# SNES_to_NES.net
KiCad netlist of a schematic drawn in EAGLE
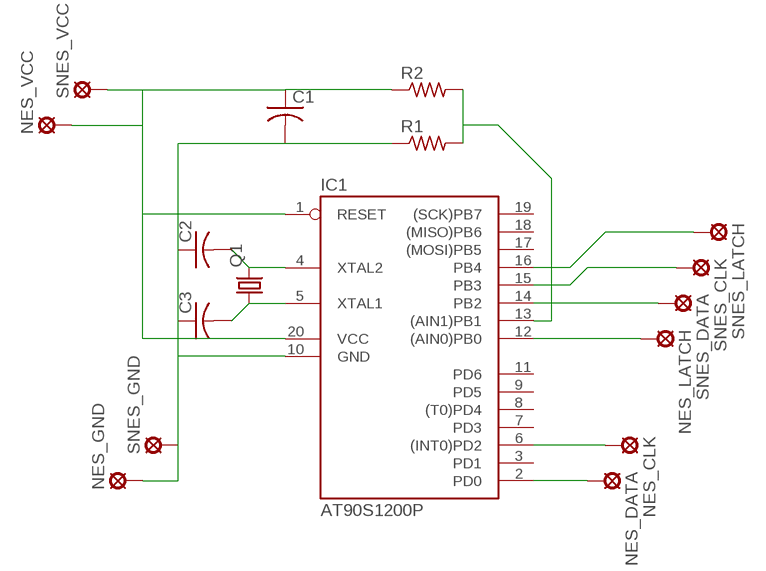
[diagram p0: schematic, sheet 1]

(export (version "E")
  (design (tool "Eeschema 10.0.6"))
  (components
    (comp (ref "C1")
      (value "C-US025_050-035X075")
      (footprint "eagle-import:C025_050-035X075")
      (libsource (lib "eagle-import") (part "C-US025_050-035X075"))
    )
    (comp (ref "C2")
      (value "C-US025-030X050")
      (footprint "eagle-import:C025-030X050")
      (libsource (lib "eagle-import") (part "C-US025-030X050"))
    )
    (comp (ref "C3")
      (value "C-US025-030X050")
      (footprint "eagle-import:C025-030X050")
      (libsource (lib "eagle-import") (part "C-US025-030X050"))
    )
    (comp (ref "IC1")
      (value "AT90S1200P")
      (footprint "eagle-import:DIL20")
      (libsource (lib "eagle-import") (part "AT90S1200P"))
    )
    (comp (ref "NES_CLK")
      (value "MCS08")
      (footprint "eagle-import:MCS08")
      (libsource (lib "eagle-import") (part "MCS08"))
    )
    (comp (ref "NES_DATA")
      (value "MCS08")
      (footprint "eagle-import:MCS08")
      (libsource (lib "eagle-import") (part "MCS08"))
    )
    (comp (ref "NES_GND")
      (value "MCS08")
      (footprint "eagle-import:MCS08")
      (libsource (lib "eagle-import") (part "MCS08"))
    )
    (comp (ref "NES_LATCH")
      (value "MCS08")
      (footprint "eagle-import:MCS08")
      (libsource (lib "eagle-import") (part "MCS08"))
    )
    (comp (ref "NES_VCC")
      (value "MCS08")
      (footprint "eagle-import:MCS08")
      (libsource (lib "eagle-import") (part "MCS08"))
    )
    (comp (ref "Q1")
      (value "CRYSTALHC49U-H")
      (footprint "eagle-import:HC49U-H")
      (libsource (lib "eagle-import") (part "CRYSTALHC49U-H"))
    )
    (comp (ref "R1")
      (value "R-US_0207/7")
      (footprint "eagle-import:0207_7")
      (libsource (lib "eagle-import") (part "R-US_0207/7"))
    )
    (comp (ref "R2")
      (value "R-US_0207/7")
      (footprint "eagle-import:0207_7")
      (libsource (lib "eagle-import") (part "R-US_0207/7"))
    )
    (comp (ref "SNES_CLK")
      (value "MCS08")
      (footprint "eagle-import:MCS08")
      (libsource (lib "eagle-import") (part "MCS08"))
    )
    (comp (ref "SNES_DATA")
      (value "MCS08")
      (footprint "eagle-import:MCS08")
      (libsource (lib "eagle-import") (part "MCS08"))
    )
    (comp (ref "SNES_GND")
      (value "MCS08")
      (footprint "eagle-import:MCS08")
      (libsource (lib "eagle-import") (part "MCS08"))
    )
    (comp (ref "SNES_LATCH")
      (value "MCS08")
      (footprint "eagle-import:MCS08")
      (libsource (lib "eagle-import") (part "MCS08"))
    )
    (comp (ref "SNES_VCC")
      (value "MCS08")
      (footprint "eagle-import:MCS08")
      (libsource (lib "eagle-import") (part "MCS08"))
    )
  )
  (nets
    (net (code "1") (name "Net-(IC1-(AIN0)PB0)") (class "Default")
      (node (ref "IC1") (pin "12") (pinfunction "(AIN0)PB0_12") (pintype "bidirectional"))
      (node (ref "NES_LATCH") (pin "MP") (pinfunction "MP_MP") (pintype "passive"))
    )
    (net (code "2") (name "Net-(IC1-(AIN1)PB1)") (class "Default")
      (node (ref "IC1") (pin "13") (pinfunction "(AIN1)PB1_13") (pintype "bidirectional"))
      (node (ref "R1") (pin "2") (pinfunction "2_2") (pintype "passive"))
      (node (ref "R2") (pin "2") (pinfunction "2_2") (pintype "passive"))
    )
    (net (code "3") (name "Net-(IC1-(INT0)PD2)") (class "Default")
      (node (ref "IC1") (pin "6") (pinfunction "(INT0)PD2_6") (pintype "bidirectional"))
      (node (ref "NES_CLK") (pin "MP") (pinfunction "MP_MP") (pintype "passive"))
    )
    (net (code "4") (name "Net-(IC1-GND)") (class "Default")
      (node (ref "C1") (pin "2") (pinfunction "2_2") (pintype "passive"))
      (node (ref "C2") (pin "1") (pinfunction "1_1") (pintype "passive"))
      (node (ref "C3") (pin "1") (pinfunction "1_1") (pintype "passive"))
      (node (ref "IC1") (pin "10") (pinfunction "GND_10") (pintype "power_in"))
      (node (ref "NES_GND") (pin "MP") (pinfunction "MP_MP") (pintype "passive"))
      (node (ref "R1") (pin "1") (pinfunction "1_1") (pintype "passive"))
      (node (ref "SNES_GND") (pin "MP") (pinfunction "MP_MP") (pintype "passive"))
    )
    (net (code "5") (name "Net-(IC1-PB2)") (class "Default")
      (node (ref "IC1") (pin "14") (pinfunction "PB2_14") (pintype "bidirectional"))
      (node (ref "SNES_DATA") (pin "MP") (pinfunction "MP_MP") (pintype "passive"))
    )
    (net (code "6") (name "Net-(IC1-PB3)") (class "Default")
      (node (ref "IC1") (pin "15") (pinfunction "PB3_15") (pintype "bidirectional"))
      (node (ref "SNES_CLK") (pin "MP") (pinfunction "MP_MP") (pintype "passive"))
    )
    (net (code "7") (name "Net-(IC1-PB4)") (class "Default")
      (node (ref "IC1") (pin "16") (pinfunction "PB4_16") (pintype "bidirectional"))
      (node (ref "SNES_LATCH") (pin "MP") (pinfunction "MP_MP") (pintype "passive"))
    )
    (net (code "8") (name "Net-(IC1-PD0)") (class "Default")
      (node (ref "IC1") (pin "2") (pinfunction "PD0_2") (pintype "bidirectional"))
      (node (ref "NES_DATA") (pin "MP") (pinfunction "MP_MP") (pintype "passive"))
    )
    (net (code "9") (name "Net-(IC1-RESET)") (class "Default")
      (node (ref "C1") (pin "1") (pinfunction "1_1") (pintype "passive"))
      (node (ref "IC1") (pin "1") (pinfunction "RESET_1") (pintype "bidirectional"))
      (node (ref "IC1") (pin "20") (pinfunction "VCC_20") (pintype "power_in"))
      (node (ref "NES_VCC") (pin "MP") (pinfunction "MP_MP") (pintype "passive"))
      (node (ref "R2") (pin "1") (pinfunction "1_1") (pintype "passive"))
      (node (ref "SNES_VCC") (pin "MP") (pinfunction "MP_MP") (pintype "passive"))
    )
    (net (code "10") (name "Net-(IC1-XTAL1)") (class "Default")
      (node (ref "C3") (pin "2") (pinfunction "2_2") (pintype "passive"))
      (node (ref "IC1") (pin "5") (pinfunction "XTAL1_5") (pintype "bidirectional"))
      (node (ref "Q1") (pin "1") (pinfunction "1_1") (pintype "passive"))
    )
    (net (code "11") (name "Net-(IC1-XTAL2)") (class "Default")
      (node (ref "C2") (pin "2") (pinfunction "2_2") (pintype "passive"))
      (node (ref "IC1") (pin "4") (pinfunction "XTAL2_4") (pintype "bidirectional"))
      (node (ref "Q1") (pin "2") (pinfunction "2_2") (pintype "passive"))
    )
    (net (code "12") (name "unconnected-(IC1-(MISO)PB6-Pad18)") (class "Default")
      (node (ref "IC1") (pin "18") (pinfunction "(MISO)PB6_18") (pintype "bidirectional"))
    )
    (net (code "13") (name "unconnected-(IC1-(MOSI)PB5-Pad17)") (class "Default")
      (node (ref "IC1") (pin "17") (pinfunction "(MOSI)PB5_17") (pintype "bidirectional"))
    )
    (net (code "14") (name "unconnected-(IC1-(SCK)PB7-Pad19)") (class "Default")
      (node (ref "IC1") (pin "19") (pinfunction "(SCK)PB7_19") (pintype "bidirectional"))
    )
    (net (code "15") (name "unconnected-(IC1-(T0)PD4-Pad8)") (class "Default")
      (node (ref "IC1") (pin "8") (pinfunction "(T0)PD4_8") (pintype "bidirectional"))
    )
    (net (code "16") (name "unconnected-(IC1-PD1-Pad3)") (class "Default")
      (node (ref "IC1") (pin "3") (pinfunction "PD1_3") (pintype "bidirectional"))
    )
    (net (code "17") (name "unconnected-(IC1-PD3-Pad7)") (class "Default")
      (node (ref "IC1") (pin "7") (pinfunction "PD3_7") (pintype "bidirectional"))
    )
    (net (code "18") (name "unconnected-(IC1-PD5-Pad9)") (class "Default")
      (node (ref "IC1") (pin "9") (pinfunction "PD5_9") (pintype "bidirectional"))
    )
    (net (code "19") (name "unconnected-(IC1-PD6-Pad11)") (class "Default")
      (node (ref "IC1") (pin "11") (pinfunction "PD6_11") (pintype "bidirectional"))
    )
  )
)
